# Charger_Board_3_Sam_Test.net
KiCad netlist of a schematic drawn in EAGLE
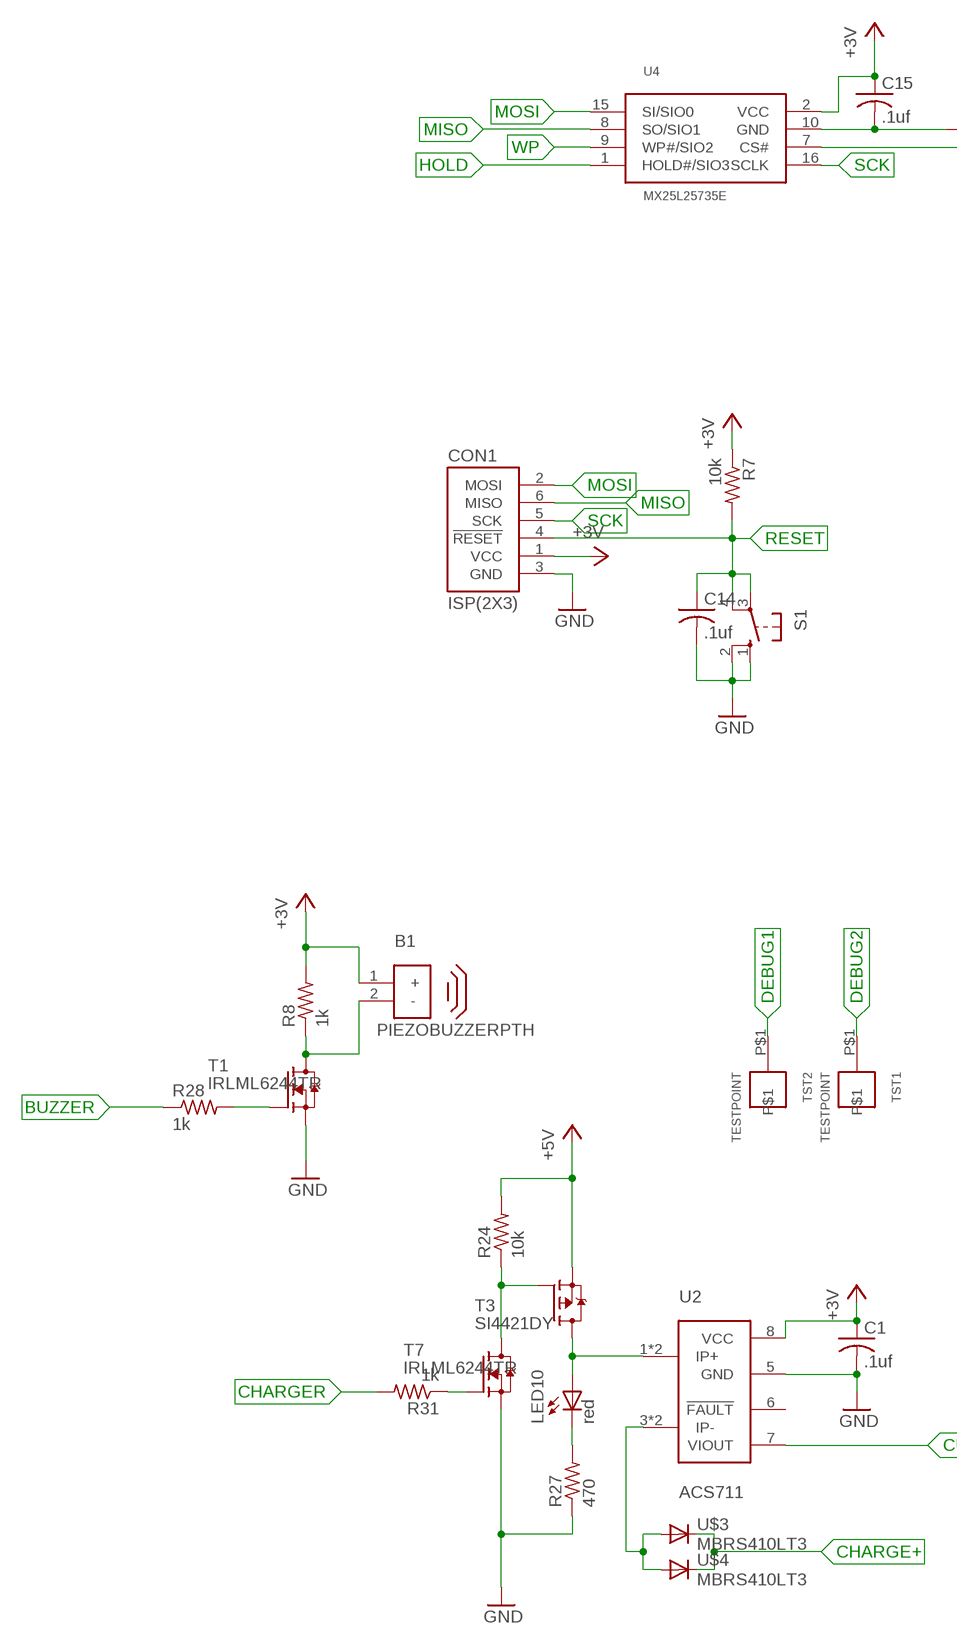
[diagram p0: schematic, sheet 1, part 1 of 2]
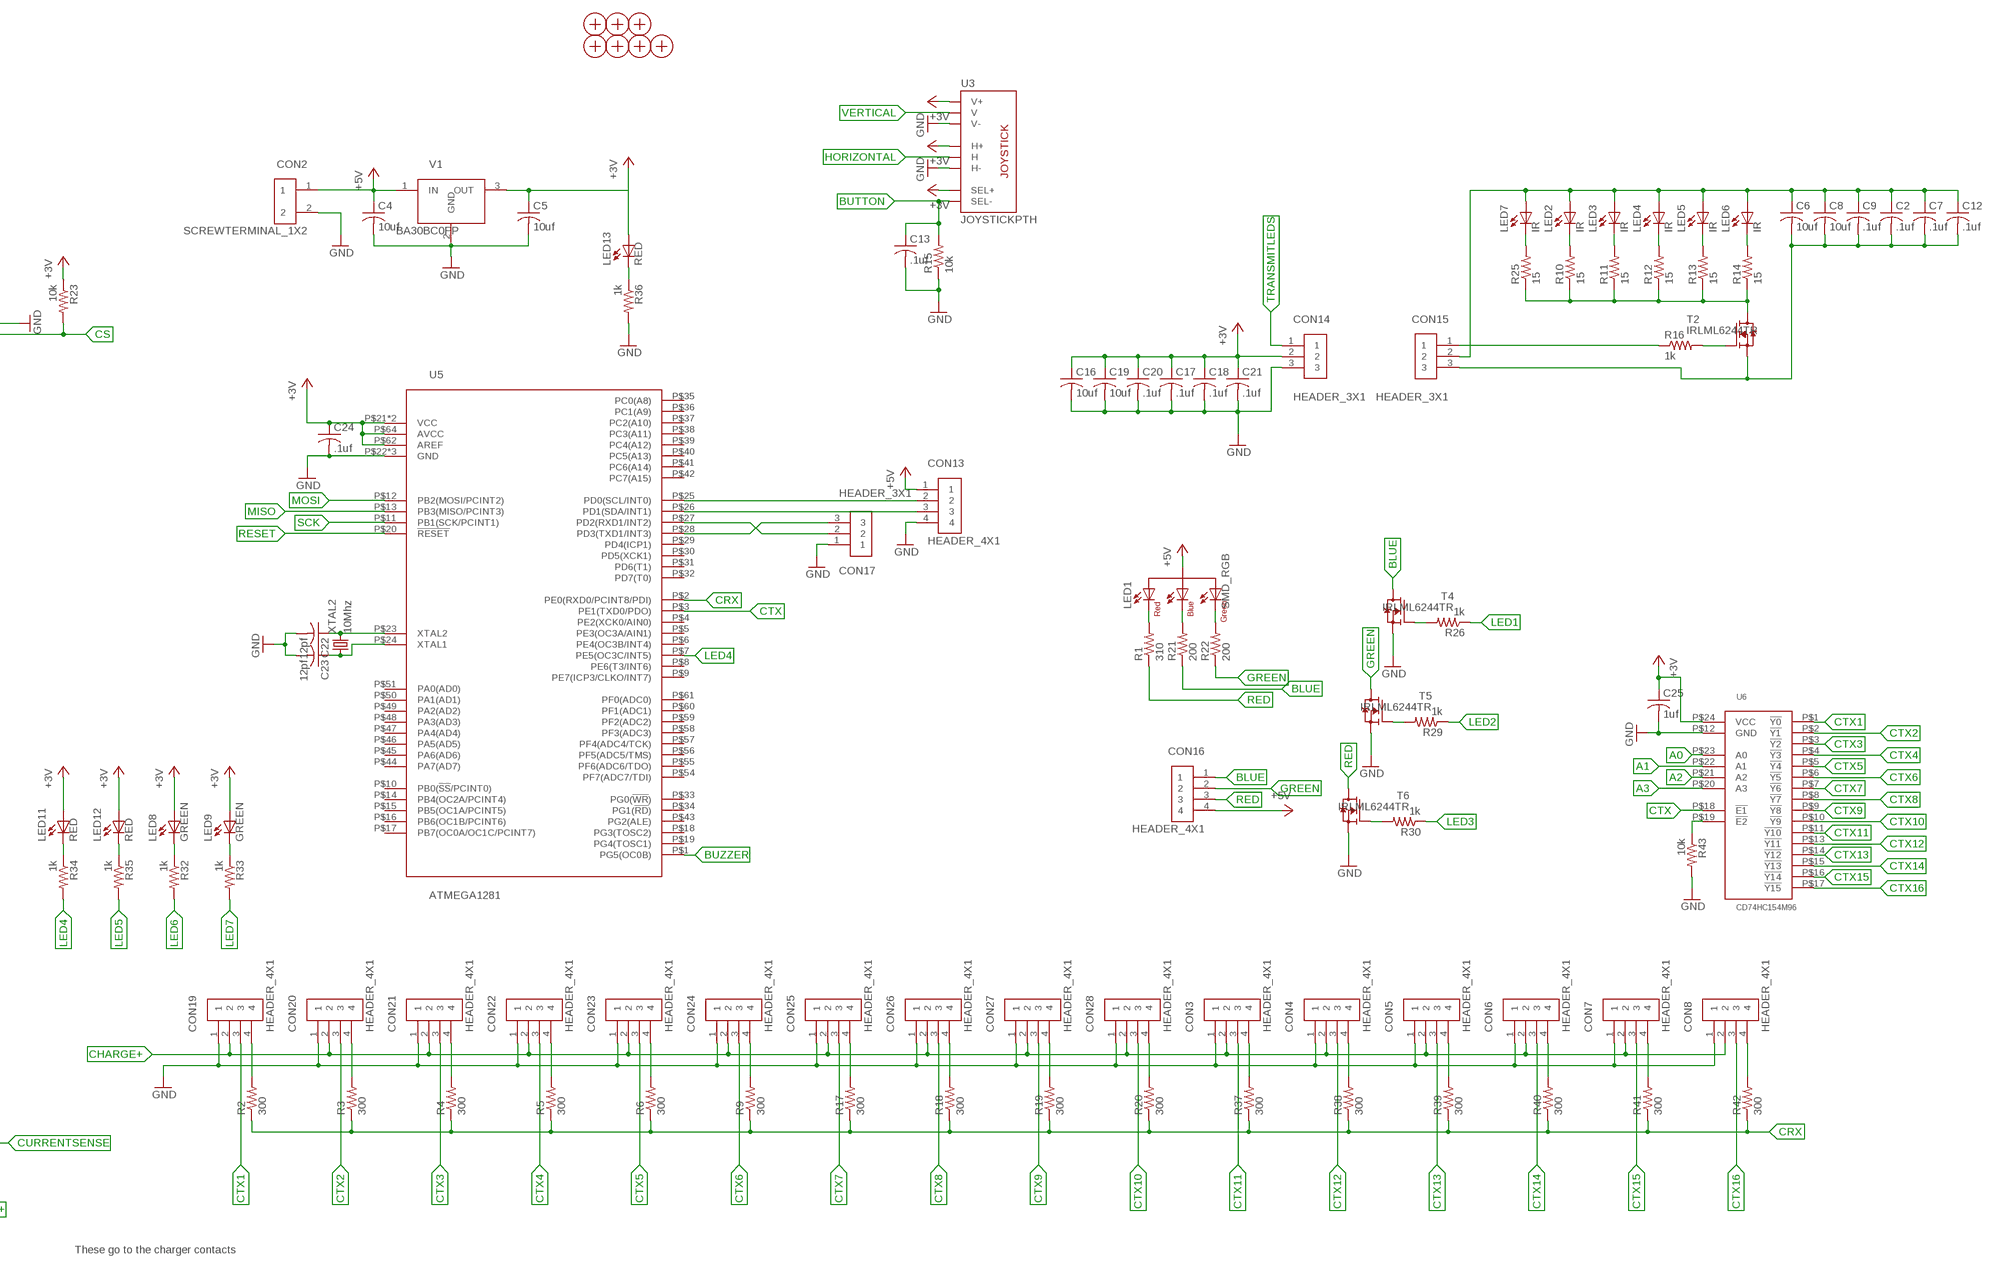
[diagram p1: schematic, sheet 1, part 2 of 2]

(export (version "E")
  (design (tool "Eeschema 10.0.6"))
  (components
    (comp (ref "B1")
      (value "PIEZOBUZZERPTH")
      (footprint "eagle-import:PIEZOBUZZER")
      (libsource (lib "eagle-import") (part "PIEZOBUZZERPTH"))
    )
    (comp (ref "C1")
      (value ".1uf")
      (footprint "eagle-import:0603")
      (libsource (lib "eagle-import") (part "CAP0603"))
    )
    (comp (ref "C2")
      (value ".1uf")
      (footprint "eagle-import:0603")
      (libsource (lib "eagle-import") (part "CAP0603"))
    )
    (comp (ref "C4")
      (value "10uf")
      (footprint "eagle-import:0805")
      (libsource (lib "eagle-import") (part "CAP0805"))
    )
    (comp (ref "C5")
      (value "10uf")
      (footprint "eagle-import:0805")
      (libsource (lib "eagle-import") (part "CAP0805"))
    )
    (comp (ref "C6")
      (value "10uf")
      (footprint "eagle-import:0805")
      (libsource (lib "eagle-import") (part "CAP0805"))
    )
    (comp (ref "C7")
      (value ".1uf")
      (footprint "eagle-import:0603")
      (libsource (lib "eagle-import") (part "CAP0603"))
    )
    (comp (ref "C8")
      (value "10uf")
      (footprint "eagle-import:0805")
      (libsource (lib "eagle-import") (part "CAP0805"))
    )
    (comp (ref "C9")
      (value ".1uf")
      (footprint "eagle-import:0603")
      (libsource (lib "eagle-import") (part "CAP0603"))
    )
    (comp (ref "C12")
      (value ".1uf")
      (footprint "eagle-import:0603")
      (libsource (lib "eagle-import") (part "CAP0603"))
    )
    (comp (ref "C13")
      (value ".1uf")
      (footprint "eagle-import:0603")
      (libsource (lib "eagle-import") (part "CAP0603"))
    )
    (comp (ref "C14")
      (value ".1uf")
      (footprint "eagle-import:0603")
      (libsource (lib "eagle-import") (part "CAP0603"))
    )
    (comp (ref "C15")
      (value ".1uf")
      (footprint "eagle-import:0603")
      (libsource (lib "eagle-import") (part "CAP0603"))
    )
    (comp (ref "C16")
      (value "10uf")
      (footprint "eagle-import:0805")
      (libsource (lib "eagle-import") (part "CAP0805"))
    )
    (comp (ref "C17")
      (value ".1uf")
      (footprint "eagle-import:0603")
      (libsource (lib "eagle-import") (part "CAP0603"))
    )
    (comp (ref "C18")
      (value ".1uf")
      (footprint "eagle-import:0603")
      (libsource (lib "eagle-import") (part "CAP0603"))
    )
    (comp (ref "C19")
      (value "10uf")
      (footprint "eagle-import:0805")
      (libsource (lib "eagle-import") (part "CAP0805"))
    )
    (comp (ref "C20")
      (value ".1uf")
      (footprint "eagle-import:0603")
      (libsource (lib "eagle-import") (part "CAP0603"))
    )
    (comp (ref "C21")
      (value ".1uf")
      (footprint "eagle-import:0603")
      (libsource (lib "eagle-import") (part "CAP0603"))
    )
    (comp (ref "C22")
      (value "12pf")
      (footprint "eagle-import:0603")
      (libsource (lib "eagle-import") (part "CAP0603"))
    )
    (comp (ref "C23")
      (value "12pf")
      (footprint "eagle-import:0603")
      (libsource (lib "eagle-import") (part "CAP0603"))
    )
    (comp (ref "C24")
      (value ".1uf")
      (footprint "eagle-import:0603")
      (libsource (lib "eagle-import") (part "CAP0603"))
    )
    (comp (ref "C25")
      (value "1uf")
      (footprint "eagle-import:0603")
      (libsource (lib "eagle-import") (part "CAP0603"))
    )
    (comp (ref "CON1")
      (value "ISP(2X3)")
      (footprint "eagle-import:PINHEADER(2X3)")
      (libsource (lib "eagle-import") (part "ISP(2X3)"))
    )
    (comp (ref "CON2")
      (value "SCREWTERMINAL_1X2")
      (footprint "eagle-import:SCREWTERMINAL_1X2")
      (libsource (lib "eagle-import") (part "SCREWTERMINAL_1X2"))
    )
    (comp (ref "CON3")
      (value "HEADER_4X1")
      (footprint "eagle-import:4PINHEADER_.100_")
      (libsource (lib "eagle-import") (part "HEADER_4X1"))
    )
    (comp (ref "CON4")
      (value "HEADER_4X1")
      (footprint "eagle-import:4PINHEADER_.100_")
      (libsource (lib "eagle-import") (part "HEADER_4X1"))
    )
    (comp (ref "CON5")
      (value "HEADER_4X1")
      (footprint "eagle-import:4PINHEADER_.100_")
      (libsource (lib "eagle-import") (part "HEADER_4X1"))
    )
    (comp (ref "CON6")
      (value "HEADER_4X1")
      (footprint "eagle-import:4PINHEADER_.100_")
      (libsource (lib "eagle-import") (part "HEADER_4X1"))
    )
    (comp (ref "CON7")
      (value "HEADER_4X1")
      (footprint "eagle-import:4PINHEADER_.100_")
      (libsource (lib "eagle-import") (part "HEADER_4X1"))
    )
    (comp (ref "CON8")
      (value "HEADER_4X1")
      (footprint "eagle-import:4PINHEADER_.100_")
      (libsource (lib "eagle-import") (part "HEADER_4X1"))
    )
    (comp (ref "CON13")
      (value "HEADER_4X1")
      (footprint "eagle-import:4PINHEADER_.100_")
      (libsource (lib "eagle-import") (part "HEADER_4X1"))
    )
    (comp (ref "CON14")
      (value "HEADER_3X1")
      (footprint "eagle-import:3PINHEADER_.100_")
      (libsource (lib "eagle-import") (part "HEADER_3X1"))
    )
    (comp (ref "CON15")
      (value "HEADER_3X1")
      (footprint "eagle-import:3PINHEADER_.100_")
      (libsource (lib "eagle-import") (part "HEADER_3X1"))
    )
    (comp (ref "CON16")
      (value "HEADER_4X1")
      (footprint "eagle-import:4PINHEADER_.100_")
      (libsource (lib "eagle-import") (part "HEADER_4X1"))
    )
    (comp (ref "CON17")
      (value "HEADER_3X1")
      (footprint "eagle-import:3PINHEADER_.100_")
      (libsource (lib "eagle-import") (part "HEADER_3X1"))
    )
    (comp (ref "CON19")
      (value "HEADER_4X1")
      (footprint "eagle-import:4PINHEADER_.100_")
      (libsource (lib "eagle-import") (part "HEADER_4X1"))
    )
    (comp (ref "CON20")
      (value "HEADER_4X1")
      (footprint "eagle-import:4PINHEADER_.100_")
      (libsource (lib "eagle-import") (part "HEADER_4X1"))
    )
    (comp (ref "CON21")
      (value "HEADER_4X1")
      (footprint "eagle-import:4PINHEADER_.100_")
      (libsource (lib "eagle-import") (part "HEADER_4X1"))
    )
    (comp (ref "CON22")
      (value "HEADER_4X1")
      (footprint "eagle-import:4PINHEADER_.100_")
      (libsource (lib "eagle-import") (part "HEADER_4X1"))
    )
    (comp (ref "CON23")
      (value "HEADER_4X1")
      (footprint "eagle-import:4PINHEADER_.100_")
      (libsource (lib "eagle-import") (part "HEADER_4X1"))
    )
    (comp (ref "CON24")
      (value "HEADER_4X1")
      (footprint "eagle-import:4PINHEADER_.100_")
      (libsource (lib "eagle-import") (part "HEADER_4X1"))
    )
    (comp (ref "CON25")
      (value "HEADER_4X1")
      (footprint "eagle-import:4PINHEADER_.100_")
      (libsource (lib "eagle-import") (part "HEADER_4X1"))
    )
    (comp (ref "CON26")
      (value "HEADER_4X1")
      (footprint "eagle-import:4PINHEADER_.100_")
      (libsource (lib "eagle-import") (part "HEADER_4X1"))
    )
    (comp (ref "CON27")
      (value "HEADER_4X1")
      (footprint "eagle-import:4PINHEADER_.100_")
      (libsource (lib "eagle-import") (part "HEADER_4X1"))
    )
    (comp (ref "CON28")
      (value "HEADER_4X1")
      (footprint "eagle-import:4PINHEADER_.100_")
      (libsource (lib "eagle-import") (part "HEADER_4X1"))
    )
    (comp (ref "H1")
      (value "MOUNTINGHOLE")
      (footprint "eagle-import:MOUNTINGHOLE")
      (libsource (lib "eagle-import") (part "MOUNTINGHOLE"))
    )
    (comp (ref "H2")
      (value "MOUNTINGHOLE")
      (footprint "eagle-import:MOUNTINGHOLE")
      (libsource (lib "eagle-import") (part "MOUNTINGHOLE"))
    )
    (comp (ref "H3")
      (value "MOUNTINGHOLE")
      (footprint "eagle-import:MOUNTINGHOLE")
      (libsource (lib "eagle-import") (part "MOUNTINGHOLE"))
    )
    (comp (ref "H4")
      (value "MOUNTINGHOLE")
      (footprint "eagle-import:MOUNTINGHOLE")
      (libsource (lib "eagle-import") (part "MOUNTINGHOLE"))
    )
    (comp (ref "H5")
      (value "MOUNTINGHOLE")
      (footprint "eagle-import:MOUNTINGHOLE")
      (libsource (lib "eagle-import") (part "MOUNTINGHOLE"))
    )
    (comp (ref "H6")
      (value "MOUNTINGHOLE")
      (footprint "eagle-import:MOUNTINGHOLE")
      (libsource (lib "eagle-import") (part "MOUNTINGHOLE"))
    )
    (comp (ref "H7")
      (value "MOUNTINGHOLE")
      (footprint "eagle-import:MOUNTINGHOLE")
      (libsource (lib "eagle-import") (part "MOUNTINGHOLE"))
    )
    (comp (ref "LED1")
      (value "SMD_RGB")
      (footprint "eagle-import:PLCC4")
      (libsource (lib "eagle-import") (part "SMD_RGB"))
    )
    (comp (ref "LED2")
      (value "IR")
      (footprint "eagle-import:5MM_LED_RA")
      (libsource (lib "eagle-import") (part "LED5MMRA"))
    )
    (comp (ref "LED3")
      (value "IR")
      (footprint "eagle-import:5MM_LED_RA")
      (libsource (lib "eagle-import") (part "LED5MMRA"))
    )
    (comp (ref "LED4")
      (value "IR")
      (footprint "eagle-import:5MM_LED_RA")
      (libsource (lib "eagle-import") (part "LED5MMRA"))
    )
    (comp (ref "LED5")
      (value "IR")
      (footprint "eagle-import:5MM_LED_RA")
      (libsource (lib "eagle-import") (part "LED5MMRA"))
    )
    (comp (ref "LED6")
      (value "IR")
      (footprint "eagle-import:5MM_LED_RA")
      (libsource (lib "eagle-import") (part "LED5MMRA"))
    )
    (comp (ref "LED7")
      (value "IR")
      (footprint "eagle-import:5MM_LED_RA")
      (libsource (lib "eagle-import") (part "LED5MMRA"))
    )
    (comp (ref "LED8")
      (value "GREEN")
      (footprint "eagle-import:LED0603")
      (libsource (lib "eagle-import") (part "LED0603"))
    )
    (comp (ref "LED9")
      (value "GREEN")
      (footprint "eagle-import:LED0603")
      (libsource (lib "eagle-import") (part "LED0603"))
    )
    (comp (ref "LED10")
      (value "red")
      (footprint "eagle-import:LED0603")
      (libsource (lib "eagle-import") (part "LED0603"))
    )
    (comp (ref "LED11")
      (value "RED")
      (footprint "eagle-import:LED0603")
      (libsource (lib "eagle-import") (part "LED0603"))
    )
    (comp (ref "LED12")
      (value "RED")
      (footprint "eagle-import:LED0603")
      (libsource (lib "eagle-import") (part "LED0603"))
    )
    (comp (ref "LED13")
      (value "RED")
      (footprint "eagle-import:LED0603")
      (libsource (lib "eagle-import") (part "LED0603"))
    )
    (comp (ref "R1")
      (value "310")
      (footprint "eagle-import:0603")
      (libsource (lib "eagle-import") (part "RES0603"))
    )
    (comp (ref "R2")
      (value "300")
      (footprint "eagle-import:0603")
      (libsource (lib "eagle-import") (part "RES0603"))
    )
    (comp (ref "R3")
      (value "300")
      (footprint "eagle-import:0603")
      (libsource (lib "eagle-import") (part "RES0603"))
    )
    (comp (ref "R4")
      (value "300")
      (footprint "eagle-import:0603")
      (libsource (lib "eagle-import") (part "RES0603"))
    )
    (comp (ref "R5")
      (value "300")
      (footprint "eagle-import:0603")
      (libsource (lib "eagle-import") (part "RES0603"))
    )
    (comp (ref "R6")
      (value "300")
      (footprint "eagle-import:0603")
      (libsource (lib "eagle-import") (part "RES0603"))
    )
    (comp (ref "R7")
      (value "10k")
      (footprint "eagle-import:0603")
      (libsource (lib "eagle-import") (part "RES0603"))
    )
    (comp (ref "R8")
      (value "1k")
      (footprint "eagle-import:0603")
      (libsource (lib "eagle-import") (part "RES0603"))
    )
    (comp (ref "R9")
      (value "300")
      (footprint "eagle-import:0603")
      (libsource (lib "eagle-import") (part "RES0603"))
    )
    (comp (ref "R10")
      (value "15")
      (footprint "eagle-import:0603")
      (libsource (lib "eagle-import") (part "RES0603"))
    )
    (comp (ref "R11")
      (value "15")
      (footprint "eagle-import:0603")
      (libsource (lib "eagle-import") (part "RES0603"))
    )
    (comp (ref "R12")
      (value "15")
      (footprint "eagle-import:0603")
      (libsource (lib "eagle-import") (part "RES0603"))
    )
    (comp (ref "R13")
      (value "15")
      (footprint "eagle-import:0603")
      (libsource (lib "eagle-import") (part "RES0603"))
    )
    (comp (ref "R14")
      (value "15")
      (footprint "eagle-import:0603")
      (libsource (lib "eagle-import") (part "RES0603"))
    )
    (comp (ref "R15")
      (value "10k")
      (footprint "eagle-import:0603")
      (libsource (lib "eagle-import") (part "RES0603"))
    )
    (comp (ref "R16")
      (value "1k")
      (footprint "eagle-import:0603")
      (libsource (lib "eagle-import") (part "RES0603"))
    )
    (comp (ref "R17")
      (value "300")
      (footprint "eagle-import:0603")
      (libsource (lib "eagle-import") (part "RES0603"))
    )
    (comp (ref "R18")
      (value "300")
      (footprint "eagle-import:0603")
      (libsource (lib "eagle-import") (part "RES0603"))
    )
    (comp (ref "R19")
      (value "300")
      (footprint "eagle-import:0603")
      (libsource (lib "eagle-import") (part "RES0603"))
    )
    (comp (ref "R20")
      (value "300")
      (footprint "eagle-import:0603")
      (libsource (lib "eagle-import") (part "RES0603"))
    )
    (comp (ref "R21")
      (value "200")
      (footprint "eagle-import:0603")
      (libsource (lib "eagle-import") (part "RES0603"))
    )
    (comp (ref "R22")
      (value "200")
      (footprint "eagle-import:0603")
      (libsource (lib "eagle-import") (part "RES0603"))
    )
    (comp (ref "R23")
      (value "10k")
      (footprint "eagle-import:0603")
      (libsource (lib "eagle-import") (part "RES0603"))
    )
    (comp (ref "R24")
      (value "10k")
      (footprint "eagle-import:0603")
      (libsource (lib "eagle-import") (part "RES0603"))
    )
    (comp (ref "R25")
      (value "15")
      (footprint "eagle-import:0603")
      (libsource (lib "eagle-import") (part "RES0603"))
    )
    (comp (ref "R26")
      (value "1k")
      (footprint "eagle-import:0603")
      (libsource (lib "eagle-import") (part "RES0603"))
    )
    (comp (ref "R27")
      (value "470")
      (footprint "eagle-import:0603")
      (libsource (lib "eagle-import") (part "RES0603"))
    )
    (comp (ref "R28")
      (value "1k")
      (footprint "eagle-import:0603")
      (libsource (lib "eagle-import") (part "RES0603"))
    )
    (comp (ref "R29")
      (value "1k")
      (footprint "eagle-import:0603")
      (libsource (lib "eagle-import") (part "RES0603"))
    )
    (comp (ref "R30")
      (value "1k")
      (footprint "eagle-import:0603")
      (libsource (lib "eagle-import") (part "RES0603"))
    )
    (comp (ref "R31")
      (value "1k")
      (footprint "eagle-import:0603")
      (libsource (lib "eagle-import") (part "RES0603"))
    )
    (comp (ref "R32")
      (value "1k")
      (footprint "eagle-import:0603")
      (libsource (lib "eagle-import") (part "RES0603"))
    )
    (comp (ref "R33")
      (value "1k")
      (footprint "eagle-import:0603")
      (libsource (lib "eagle-import") (part "RES0603"))
    )
    (comp (ref "R34")
      (value "1k")
      (footprint "eagle-import:0603")
      (libsource (lib "eagle-import") (part "RES0603"))
    )
    (comp (ref "R35")
      (value "1k")
      (footprint "eagle-import:0603")
      (libsource (lib "eagle-import") (part "RES0603"))
    )
    (comp (ref "R36")
      (value "1k")
      (footprint "eagle-import:0603")
      (libsource (lib "eagle-import") (part "RES0603"))
    )
    (comp (ref "R37")
      (value "300")
      (footprint "eagle-import:0603")
      (libsource (lib "eagle-import") (part "RES0603"))
    )
    (comp (ref "R38")
      (value "300")
      (footprint "eagle-import:0603")
      (libsource (lib "eagle-import") (part "RES0603"))
    )
    (comp (ref "R39")
      (value "300")
      (footprint "eagle-import:0603")
      (libsource (lib "eagle-import") (part "RES0603"))
    )
    (comp (ref "R40")
      (value "300")
      (footprint "eagle-import:0603")
      (libsource (lib "eagle-import") (part "RES0603"))
    )
    (comp (ref "R41")
      (value "300")
      (footprint "eagle-import:0603")
      (libsource (lib "eagle-import") (part "RES0603"))
    )
    (comp (ref "R42")
      (value "300")
      (footprint "eagle-import:0603")
      (libsource (lib "eagle-import") (part "RES0603"))
    )
    (comp (ref "R43")
      (value "10k")
      (footprint "eagle-import:0603")
      (libsource (lib "eagle-import") (part "RES0603"))
    )
    (comp (ref "S1")
      (value "10-XX")
      (footprint "eagle-import:B3F-10XX")
      (fields (field (name "MPN") "B3F-1000"))
      (libsource (lib "eagle-import") (part "10-XX"))
    )
    (comp (ref "T1")
      (value "IRLML6244TR")
      (footprint "eagle-import:SOT23")
      (libsource (lib "eagle-import") (part "IRLML6244TR"))
    )
    (comp (ref "T2")
      (value "IRLML6244TR")
      (footprint "eagle-import:SOT23")
      (libsource (lib "eagle-import") (part "IRLML6244TR"))
    )
    (comp (ref "T3")
      (value "SI4421DY")
      (footprint "eagle-import:S0-8")
      (libsource (lib "eagle-import") (part "SI4421DY"))
    )
    (comp (ref "T4")
      (value "IRLML6244TR")
      (footprint "eagle-import:SOT23")
      (libsource (lib "eagle-import") (part "IRLML6244TR"))
    )
    (comp (ref "T5")
      (value "IRLML6244TR")
      (footprint "eagle-import:SOT23")
      (libsource (lib "eagle-import") (part "IRLML6244TR"))
    )
    (comp (ref "T6")
      (value "IRLML6244TR")
      (footprint "eagle-import:SOT23")
      (libsource (lib "eagle-import") (part "IRLML6244TR"))
    )
    (comp (ref "T7")
      (value "IRLML6244TR")
      (footprint "eagle-import:SOT23")
      (libsource (lib "eagle-import") (part "IRLML6244TR"))
    )
    (comp (ref "TST1")
      (value "TESTPOINT")
      (footprint "eagle-import:TESTPOINT")
      (libsource (lib "eagle-import") (part "TESTPOINT"))
    )
    (comp (ref "TST2")
      (value "TESTPOINT")
      (footprint "eagle-import:TESTPOINT")
      (libsource (lib "eagle-import") (part "TESTPOINT"))
    )
    (comp (ref "U$3")
      (value "MBRS410LT3")
      (footprint "eagle-import:SMD_DIODE")
      (libsource (lib "eagle-import") (part "MBRS410LT3"))
    )
    (comp (ref "U$4")
      (value "MBRS410LT3")
      (footprint "eagle-import:SMD_DIODE")
      (libsource (lib "eagle-import") (part "MBRS410LT3"))
    )
    (comp (ref "U2")
      (value "ACS711")
      (footprint "eagle-import:8SOIC")
      (libsource (lib "eagle-import") (part "ACS711"))
    )
    (comp (ref "U3")
      (value "JOYSTICKPTH")
      (footprint "eagle-import:JOYSTICK")
      (libsource (lib "eagle-import") (part "JOYSTICKPTH"))
    )
    (comp (ref "U4")
      (value "MX25L25735E")
      (footprint "eagle-import:SOIC16R")
      (libsource (lib "eagle-import") (part "MX25L25735E"))
    )
    (comp (ref "U5")
      (value "ATMEGA1281")
      (footprint "eagle-import:TQFP64")
      (libsource (lib "eagle-import") (part "ATMEGA1281"))
    )
    (comp (ref "U6")
      (value "CD74HC154M96")
      (footprint "eagle-import:24SOIC")
      (libsource (lib "eagle-import") (part "CD74HC154M96"))
    )
    (comp (ref "V1")
      (value "BA30BC0FP")
      (footprint "eagle-import:DPAK")
      (libsource (lib "eagle-import") (part "BA30BC0FP"))
    )
    (comp (ref "XTAL2")
      (value "10Mhz")
      (footprint "eagle-import:SMDXTAL")
      (libsource (lib "eagle-import") (part "NX5032GA-10.000000MHZ"))
    )
  )
  (nets
    (net (code "1") (name "+3V") (class "Default")
      (node (ref "B1") (pin "1") (pinfunction "+_1") (pintype "bidirectional"))
      (node (ref "C1") (pin "1") (pinfunction "1_1") (pintype "passive"))
      (node (ref "C15") (pin "1") (pinfunction "1_1") (pintype "passive"))
      (node (ref "C16") (pin "1") (pinfunction "1_1") (pintype "passive"))
      (node (ref "C17") (pin "1") (pinfunction "1_1") (pintype "passive"))
      (node (ref "C18") (pin "1") (pinfunction "1_1") (pintype "passive"))
      (node (ref "C19") (pin "1") (pinfunction "1_1") (pintype "passive"))
      (node (ref "C20") (pin "1") (pinfunction "1_1") (pintype "passive"))
      (node (ref "C21") (pin "1") (pinfunction "1_1") (pintype "passive"))
      (node (ref "C24") (pin "1") (pinfunction "1_1") (pintype "passive"))
      (node (ref "C25") (pin "1") (pinfunction "1_1") (pintype "passive"))
      (node (ref "C5") (pin "1") (pinfunction "1_1") (pintype "passive"))
      (node (ref "CON1") (pin "1") (pinfunction "VCC_1") (pintype "bidirectional"))
      (node (ref "CON14") (pin "2") (pinfunction "2_2") (pintype "bidirectional"))
      (node (ref "LED11") (pin "2") (pinfunction "A_2") (pintype "passive"))
      (node (ref "LED12") (pin "2") (pinfunction "A_2") (pintype "passive"))
      (node (ref "LED13") (pin "2") (pinfunction "A_2") (pintype "passive"))
      (node (ref "LED8") (pin "2") (pinfunction "A_2") (pintype "passive"))
      (node (ref "LED9") (pin "2") (pinfunction "A_2") (pintype "passive"))
      (node (ref "R23") (pin "1") (pinfunction "1_1") (pintype "passive"))
      (node (ref "R7") (pin "1") (pinfunction "1_1") (pintype "passive"))
      (node (ref "R8") (pin "2") (pinfunction "2_2") (pintype "passive"))
      (node (ref "U2") (pin "8") (pinfunction "VCC_8") (pintype "bidirectional"))
      (node (ref "U3") (pin "B1A") (pinfunction "SEL+_B1A") (pintype "bidirectional"))
      (node (ref "U3") (pin "H1") (pinfunction "H+_H1") (pintype "bidirectional"))
      (node (ref "U3") (pin "V1") (pinfunction "V+_V1") (pintype "bidirectional"))
      (node (ref "U4") (pin "2") (pinfunction "VCC_2") (pintype "bidirectional"))
      (node (ref "U5") (pin "P$21") (pinfunction "VCC_P$21") (pintype "bidirectional"))
      (node (ref "U5") (pin "P$52") (pinfunction "VCC_P$52") (pintype "bidirectional"))
      (node (ref "U5") (pin "P$62") (pinfunction "AREF_P$62") (pintype "bidirectional"))
      (node (ref "U5") (pin "P$64") (pinfunction "AVCC_P$64") (pintype "bidirectional"))
      (node (ref "U6") (pin "P$24") (pinfunction "VCC_P$24") (pintype "bidirectional"))
      (node (ref "V1") (pin "3") (pinfunction "OUT_3") (pintype "bidirectional"))
    )
    (net (code "2") (name "+5V") (class "Default")
      (node (ref "C4") (pin "1") (pinfunction "1_1") (pintype "passive"))
      (node (ref "CON13") (pin "1") (pinfunction "1_1") (pintype "bidirectional"))
      (node (ref "CON16") (pin "4") (pinfunction "4_4") (pintype "bidirectional"))
      (node (ref "CON2") (pin "1") (pinfunction "1_1") (pintype "bidirectional"))
      (node (ref "LED1") (pin "2") (pinfunction "COMMONANODE_2") (pintype "passive"))
      (node (ref "R24") (pin "2") (pinfunction "2_2") (pintype "passive"))
      (node (ref "T3") (pin "1") (pinfunction "S_1") (pintype "passive"))
      (node (ref "T3") (pin "2") (pinfunction "S_2") (pintype "passive"))
      (node (ref "T3") (pin "3") (pinfunction "S_3") (pintype "passive"))
      (node (ref "V1") (pin "1") (pinfunction "IN_1") (pintype "bidirectional"))
    )
    (net (code "3") (name "A0") (class "Default")
      (node (ref "U6") (pin "P$23") (pinfunction "A0_P$23") (pintype "bidirectional"))
    )
    (net (code "4") (name "A1") (class "Default")
      (node (ref "U6") (pin "P$22") (pinfunction "A1_P$22") (pintype "bidirectional"))
    )
    (net (code "5") (name "A2") (class "Default")
      (node (ref "U6") (pin "P$21") (pinfunction "A2_P$21") (pintype "bidirectional"))
    )
    (net (code "6") (name "A3") (class "Default")
      (node (ref "U6") (pin "P$20") (pinfunction "A3_P$20") (pintype "bidirectional"))
    )
    (net (code "7") (name "BLUE") (class "Default")
      (node (ref "CON16") (pin "1") (pinfunction "1_1") (pintype "bidirectional"))
      (node (ref "R21") (pin "1") (pinfunction "1_1") (pintype "passive"))
      (node (ref "T4") (pin "3") (pinfunction "D_3") (pintype "passive"))
    )
    (net (code "8") (name "BUTTON") (class "Default")
      (node (ref "C13") (pin "1") (pinfunction "1_1") (pintype "passive"))
      (node (ref "R15") (pin "2") (pinfunction "2_2") (pintype "passive"))
      (node (ref "U3") (pin "B2A") (pinfunction "SEL-_B2A") (pintype "bidirectional"))
    )
    (net (code "9") (name "BUZZER") (class "Default")
      (node (ref "R28") (pin "1") (pinfunction "1_1") (pintype "passive"))
      (node (ref "U5") (pin "P$1") (pinfunction "PG5(OC0B)_P$1") (pintype "bidirectional"))
    )
    (net (code "10") (name "CHARGE+") (class "Default")
      (node (ref "CON19") (pin "2") (pinfunction "2_2") (pintype "bidirectional"))
      (node (ref "CON20") (pin "2") (pinfunction "2_2") (pintype "bidirectional"))
      (node (ref "CON21") (pin "2") (pinfunction "2_2") (pintype "bidirectional"))
      (node (ref "CON22") (pin "2") (pinfunction "2_2") (pintype "bidirectional"))
      (node (ref "CON23") (pin "2") (pinfunction "2_2") (pintype "bidirectional"))
      (node (ref "CON24") (pin "2") (pinfunction "2_2") (pintype "bidirectional"))
      (node (ref "CON25") (pin "2") (pinfunction "2_2") (pintype "bidirectional"))
      (node (ref "CON26") (pin "2") (pinfunction "2_2") (pintype "bidirectional"))
      (node (ref "CON27") (pin "2") (pinfunction "2_2") (pintype "bidirectional"))
      (node (ref "CON28") (pin "2") (pinfunction "2_2") (pintype "bidirectional"))
      (node (ref "CON3") (pin "2") (pinfunction "2_2") (pintype "bidirectional"))
      (node (ref "CON4") (pin "2") (pinfunction "2_2") (pintype "bidirectional"))
      (node (ref "CON5") (pin "2") (pinfunction "2_2") (pintype "bidirectional"))
      (node (ref "CON6") (pin "2") (pinfunction "2_2") (pintype "bidirectional"))
      (node (ref "CON7") (pin "2") (pinfunction "2_2") (pintype "bidirectional"))
      (node (ref "CON8") (pin "2") (pinfunction "2_2") (pintype "bidirectional"))
      (node (ref "U$3") (pin "2") (pinfunction "C_2") (pintype "passive"))
      (node (ref "U$4") (pin "2") (pinfunction "C_2") (pintype "passive"))
    )
    (net (code "11") (name "CHARGER") (class "Default")
      (node (ref "R31") (pin "2") (pinfunction "2_2") (pintype "passive"))
    )
    (net (code "12") (name "CRX") (class "Default")
      (node (ref "R17") (pin "1") (pinfunction "1_1") (pintype "passive"))
      (node (ref "R18") (pin "1") (pinfunction "1_1") (pintype "passive"))
      (node (ref "R19") (pin "1") (pinfunction "1_1") (pintype "passive"))
      (node (ref "R2") (pin "1") (pinfunction "1_1") (pintype "passive"))
      (node (ref "R20") (pin "1") (pinfunction "1_1") (pintype "passive"))
      (node (ref "R3") (pin "1") (pinfunction "1_1") (pintype "passive"))
      (node (ref "R37") (pin "1") (pinfunction "1_1") (pintype "passive"))
      (node (ref "R38") (pin "1") (pinfunction "1_1") (pintype "passive"))
      (node (ref "R39") (pin "1") (pinfunction "1_1") (pintype "passive"))
      (node (ref "R4") (pin "1") (pinfunction "1_1") (pintype "passive"))
      (node (ref "R40") (pin "1") (pinfunction "1_1") (pintype "passive"))
      (node (ref "R41") (pin "1") (pinfunction "1_1") (pintype "passive"))
      (node (ref "R42") (pin "1") (pinfunction "1_1") (pintype "passive"))
      (node (ref "R5") (pin "1") (pinfunction "1_1") (pintype "passive"))
      (node (ref "R6") (pin "1") (pinfunction "1_1") (pintype "passive"))
      (node (ref "R9") (pin "1") (pinfunction "1_1") (pintype "passive"))
      (node (ref "U5") (pin "P$2") (pinfunction "PE0(RXD0/PCINT8/PDI)_P$2") (pintype "bidirectional"))
    )
    (net (code "13") (name "CS") (class "Default")
      (node (ref "R23") (pin "2") (pinfunction "2_2") (pintype "passive"))
      (node (ref "U4") (pin "7") (pinfunction "CS#_7") (pintype "bidirectional"))
    )
    (net (code "14") (name "CTX") (class "Default")
      (node (ref "U5") (pin "P$3") (pinfunction "PE1(TXD0/PDO)_P$3") (pintype "bidirectional"))
      (node (ref "U6") (pin "P$18") (pinfunction "~{E1}_P$18") (pintype "bidirectional"))
    )
    (net (code "15") (name "CTX1") (class "Default")
      (node (ref "CON19") (pin "3") (pinfunction "3_3") (pintype "bidirectional"))
      (node (ref "U6") (pin "P$1") (pinfunction "~{Y0}_P$1") (pintype "bidirectional"))
    )
    (net (code "16") (name "CTX2") (class "Default")
      (node (ref "CON20") (pin "3") (pinfunction "3_3") (pintype "bidirectional"))
      (node (ref "U6") (pin "P$2") (pinfunction "~{Y1}_P$2") (pintype "bidirectional"))
    )
    (net (code "17") (name "CTX3") (class "Default")
      (node (ref "CON21") (pin "3") (pinfunction "3_3") (pintype "bidirectional"))
      (node (ref "U6") (pin "P$3") (pinfunction "~{Y2}_P$3") (pintype "bidirectional"))
    )
    (net (code "18") (name "CTX4") (class "Default")
      (node (ref "CON22") (pin "3") (pinfunction "3_3") (pintype "bidirectional"))
      (node (ref "U6") (pin "P$4") (pinfunction "~{Y3}_P$4") (pintype "bidirectional"))
    )
    (net (code "19") (name "CTX5") (class "Default")
      (node (ref "CON23") (pin "3") (pinfunction "3_3") (pintype "bidirectional"))
      (node (ref "U6") (pin "P$5") (pinfunction "~{Y4}_P$5") (pintype "bidirectional"))
    )
    (net (code "20") (name "CTX6") (class "Default")
      (node (ref "CON24") (pin "3") (pinfunction "3_3") (pintype "bidirectional"))
      (node (ref "U6") (pin "P$6") (pinfunction "~{Y5}_P$6") (pintype "bidirectional"))
    )
    (net (code "21") (name "CTX7") (class "Default")
      (node (ref "CON25") (pin "3") (pinfunction "3_3") (pintype "bidirectional"))
      (node (ref "U6") (pin "P$7") (pinfunction "~{Y6}_P$7") (pintype "bidirectional"))
    )
    (net (code "22") (name "CTX8") (class "Default")
      (node (ref "CON26") (pin "3") (pinfunction "3_3") (pintype "bidirectional"))
      (node (ref "U6") (pin "P$8") (pinfunction "~{Y7}_P$8") (pintype "bidirectional"))
    )
    (net (code "23") (name "CTX9") (class "Default")
      (node (ref "CON27") (pin "3") (pinfunction "3_3") (pintype "bidirectional"))
      (node (ref "U6") (pin "P$9") (pinfunction "~{Y8}_P$9") (pintype "bidirectional"))
    )
    (net (code "24") (name "CTX10") (class "Default")
      (node (ref "CON28") (pin "3") (pinfunction "3_3") (pintype "bidirectional"))
      (node (ref "U6") (pin "P$10") (pinfunction "~{Y9}_P$10") (pintype "bidirectional"))
    )
    (net (code "25") (name "CTX11") (class "Default")
      (node (ref "CON3") (pin "3") (pinfunction "3_3") (pintype "bidirectional"))
      (node (ref "U6") (pin "P$11") (pinfunction "~{Y10}_P$11") (pintype "bidirectional"))
    )
    (net (code "26") (name "CTX12") (class "Default")
      (node (ref "CON4") (pin "3") (pinfunction "3_3") (pintype "bidirectional"))
      (node (ref "U6") (pin "P$13") (pinfunction "~{Y11}_P$13") (pintype "bidirectional"))
    )
    (net (code "27") (name "CTX13") (class "Default")
      (node (ref "CON5") (pin "3") (pinfunction "3_3") (pintype "bidirectional"))
      (node (ref "U6") (pin "P$14") (pinfunction "~{Y12}_P$14") (pintype "bidirectional"))
    )
    (net (code "28") (name "CTX14") (class "Default")
      (node (ref "CON6") (pin "3") (pinfunction "3_3") (pintype "bidirectional"))
      (node (ref "U6") (pin "P$15") (pinfunction "~{Y13}_P$15") (pintype "bidirectional"))
    )
    (net (code "29") (name "CTX15") (class "Default")
      (node (ref "CON7") (pin "3") (pinfunction "3_3") (pintype "bidirectional"))
      (node (ref "U6") (pin "P$16") (pinfunction "~{Y14}_P$16") (pintype "bidirectional"))
    )
    (net (code "30") (name "CTX16") (class "Default")
      (node (ref "CON8") (pin "3") (pinfunction "3_3") (pintype "bidirectional"))
      (node (ref "U6") (pin "P$17") (pinfunction "~{Y15}_P$17") (pintype "bidirectional"))
    )
    (net (code "31") (name "CURRENTSENSE") (class "Default")
      (node (ref "U2") (pin "7") (pinfunction "VIOUT_7") (pintype "bidirectional"))
    )
    (net (code "32") (name "DEBUG1") (class "Default")
      (node (ref "TST2") (pin "P$1") (pinfunction "P$1_P$1") (pintype "bidirectional"))
    )
    (net (code "33") (name "DEBUG2") (class "Default")
      (node (ref "TST1") (pin "P$1") (pinfunction "P$1_P$1") (pintype "bidirectional"))
    )
    (net (code "34") (name "GND") (class "Default")
      (node (ref "C1") (pin "2") (pinfunction "2_2") (pintype "passive"))
      (node (ref "C13") (pin "2") (pinfunction "2_2") (pintype "passive"))
      (node (ref "C14") (pin "2") (pinfunction "2_2") (pintype "passive"))
      (node (ref "C15") (pin "2") (pinfunction "2_2") (pintype "passive"))
      (node (ref "C16") (pin "2") (pinfunction "2_2") (pintype "passive"))
      (node (ref "C17") (pin "2") (pinfunction "2_2") (pintype "passive"))
      (node (ref "C18") (pin "2") (pinfunction "2_2") (pintype "passive"))
      (node (ref "C19") (pin "2") (pinfunction "2_2") (pintype "passive"))
      (node (ref "C20") (pin "2") (pinfunction "2_2") (pintype "passive"))
      (node (ref "C21") (pin "2") (pinfunction "2_2") (pintype "passive"))
      (node (ref "C22") (pin "2") (pinfunction "2_2") (pintype "passive"))
      (node (ref "C23") (pin "2") (pinfunction "2_2") (pintype "passive"))
      (node (ref "C24") (pin "2") (pinfunction "2_2") (pintype "passive"))
      (node (ref "C25") (pin "2") (pinfunction "2_2") (pintype "passive"))
      (node (ref "C4") (pin "2") (pinfunction "2_2") (pintype "passive"))
      (node (ref "C5") (pin "2") (pinfunction "2_2") (pintype "passive"))
      (node (ref "CON1") (pin "3") (pinfunction "GND_3") (pintype "bidirectional"))
      (node (ref "CON13") (pin "4") (pinfunction "4_4") (pintype "bidirectional"))
      (node (ref "CON14") (pin "3") (pinfunction "3_3") (pintype "bidirectional"))
      (node (ref "CON17") (pin "1") (pinfunction "1_1") (pintype "bidirectional"))
      (node (ref "CON19") (pin "1") (pinfunction "1_1") (pintype "bidirectional"))
      (node (ref "CON2") (pin "2") (pinfunction "2_2") (pintype "bidirectional"))
      (node (ref "CON20") (pin "1") (pinfunction "1_1") (pintype "bidirectional"))
      (node (ref "CON21") (pin "1") (pinfunction "1_1") (pintype "bidirectional"))
      (node (ref "CON22") (pin "1") (pinfunction "1_1") (pintype "bidirectional"))
      (node (ref "CON23") (pin "1") (pinfunction "1_1") (pintype "bidirectional"))
      (node (ref "CON24") (pin "1") (pinfunction "1_1") (pintype "bidirectional"))
      (node (ref "CON25") (pin "1") (pinfunction "1_1") (pintype "bidirectional"))
      (node (ref "CON26") (pin "1") (pinfunction "1_1") (pintype "bidirectional"))
      (node (ref "CON27") (pin "1") (pinfunction "1_1") (pintype "bidirectional"))
      (node (ref "CON28") (pin "1") (pinfunction "1_1") (pintype "bidirectional"))
      (node (ref "CON3") (pin "1") (pinfunction "1_1") (pintype "bidirectional"))
      (node (ref "CON4") (pin "1") (pinfunction "1_1") (pintype "bidirectional"))
      (node (ref "CON5") (pin "1") (pinfunction "1_1") (pintype "bidirectional"))
      (node (ref "CON6") (pin "1") (pinfunction "1_1") (pintype "bidirectional"))
      (node (ref "CON7") (pin "1") (pinfunction "1_1") (pintype "bidirectional"))
      (node (ref "CON8") (pin "1") (pinfunction "1_1") (pintype "bidirectional"))
      (node (ref "R15") (pin "1") (pinfunction "1_1") (pintype "passive"))
      (node (ref "R27") (pin "1") (pinfunction "1_1") (pintype "passive"))
      (node (ref "R36") (pin "2") (pinfunction "2_2") (pintype "passive"))
      (node (ref "R43") (pin "2") (pinfunction "2_2") (pintype "passive"))
      (node (ref "S1") (pin "1") (pinfunction "S_1") (pintype "passive"))
      (node (ref "S1") (pin "2") (pinfunction "S1_2") (pintype "passive"))
      (node (ref "T1") (pin "2") (pinfunction "S_2") (pintype "passive"))
      (node (ref "T4") (pin "2") (pinfunction "S_2") (pintype "passive"))
      (node (ref "T5") (pin "2") (pinfunction "S_2") (pintype "passive"))
      (node (ref "T6") (pin "2") (pinfunction "S_2") (pintype "passive"))
      (node (ref "T7") (pin "2") (pinfunction "S_2") (pintype "passive"))
      (node (ref "U2") (pin "5") (pinfunction "GND_5") (pintype "bidirectional"))
      (node (ref "U3") (pin "H3") (pinfunction "H-_H3") (pintype "bidirectional"))
      (node (ref "U3") (pin "V3") (pinfunction "V-_V3") (pintype "bidirectional"))
      (node (ref "U4") (pin "10") (pinfunction "GND_10") (pintype "bidirectional"))
      (node (ref "U5") (pin "P$22") (pinfunction "GND_P$22") (pintype "bidirectional"))
      (node (ref "U5") (pin "P$53") (pinfunction "GND_P$53") (pintype "bidirectional"))
      (node (ref "U5") (pin "P$63") (pinfunction "GND_P$63") (pintype "bidirectional"))
      (node (ref "U6") (pin "P$12") (pinfunction "GND_P$12") (pintype "bidirectional"))
      (node (ref "V1") (pin "2") (pinfunction "GND_2") (pintype "bidirectional"))
    )
    (net (code "35") (name "GREEN") (class "Default")
      (node (ref "CON16") (pin "2") (pinfunction "2_2") (pintype "bidirectional"))
      (node (ref "R22") (pin "1") (pinfunction "1_1") (pintype "passive"))
      (node (ref "T5") (pin "3") (pinfunction "D_3") (pintype "passive"))
    )
    (net (code "36") (name "HOLD") (class "Default")
      (node (ref "U4") (pin "1") (pinfunction "HOLD#/SIO3_1") (pintype "bidirectional"))
    )
    (net (code "37") (name "HORIZONTAL") (class "Default")
      (node (ref "U3") (pin "H2") (pinfunction "H_H2") (pintype "bidirectional"))
    )
    (net (code "38") (name "LED1") (class "Default")
      (node (ref "R26") (pin "1") (pinfunction "1_1") (pintype "passive"))
    )
    (net (code "39") (name "LED2") (class "Default")
      (node (ref "R29") (pin "1") (pinfunction "1_1") (pintype "passive"))
    )
    (net (code "40") (name "LED3") (class "Default")
      (node (ref "R30") (pin "1") (pinfunction "1_1") (pintype "passive"))
    )
    (net (code "41") (name "LED4") (class "Default")
      (node (ref "R34") (pin "2") (pinfunction "2_2") (pintype "passive"))
      (node (ref "U5") (pin "P$7") (pinfunction "PE5(OC3C/INT5)_P$7") (pintype "bidirectional"))
    )
    (net (code "42") (name "LED5") (class "Default")
      (node (ref "R35") (pin "2") (pinfunction "2_2") (pintype "passive"))
    )
    (net (code "43") (name "LED6") (class "Default")
      (node (ref "R32") (pin "2") (pinfunction "2_2") (pintype "passive"))
    )
    (net (code "44") (name "LED7") (class "Default")
      (node (ref "R33") (pin "2") (pinfunction "2_2") (pintype "passive"))
    )
    (net (code "45") (name "MISO") (class "Default")
      (node (ref "CON1") (pin "6") (pinfunction "MISO_6") (pintype "bidirectional"))
      (node (ref "U4") (pin "8") (pinfunction "SO/SIO1_8") (pintype "bidirectional"))
      (node (ref "U5") (pin "P$13") (pinfunction "PB3(MISO/PCINT3)_P$13") (pintype "bidirectional"))
    )
    (net (code "46") (name "MOSI") (class "Default")
      (node (ref "CON1") (pin "2") (pinfunction "MOSI_2") (pintype "bidirectional"))
      (node (ref "U4") (pin "15") (pinfunction "SI/SIO0_15") (pintype "bidirectional"))
      (node (ref "U5") (pin "P$12") (pinfunction "PB2(MOSI/PCINT2)_P$12") (pintype "bidirectional"))
    )
    (net (code "47") (name "Net-(B1--)") (class "Default")
      (node (ref "B1") (pin "2") (pinfunction "-_2") (pintype "bidirectional"))
      (node (ref "R8") (pin "1") (pinfunction "1_1") (pintype "passive"))
      (node (ref "T1") (pin "3") (pinfunction "D_3") (pintype "passive"))
    )
    (net (code "48") (name "Net-(CON3-Pad4)") (class "Default")
      (node (ref "CON3") (pin "4") (pinfunction "4_4") (pintype "bidirectional"))
      (node (ref "R37") (pin "2") (pinfunction "2_2") (pintype "passive"))
    )
    (net (code "49") (name "Net-(CON4-Pad4)") (class "Default")
      (node (ref "CON4") (pin "4") (pinfunction "4_4") (pintype "bidirectional"))
      (node (ref "R38") (pin "2") (pinfunction "2_2") (pintype "passive"))
    )
    (net (code "50") (name "Net-(CON5-Pad4)") (class "Default")
      (node (ref "CON5") (pin "4") (pinfunction "4_4") (pintype "bidirectional"))
      (node (ref "R39") (pin "2") (pinfunction "2_2") (pintype "passive"))
    )
    (net (code "51") (name "Net-(CON6-Pad4)") (class "Default")
      (node (ref "CON6") (pin "4") (pinfunction "4_4") (pintype "bidirectional"))
      (node (ref "R40") (pin "2") (pinfunction "2_2") (pintype "passive"))
    )
    (net (code "52") (name "Net-(CON7-Pad4)") (class "Default")
      (node (ref "CON7") (pin "4") (pinfunction "4_4") (pintype "bidirectional"))
      (node (ref "R41") (pin "2") (pinfunction "2_2") (pintype "passive"))
    )
    (net (code "53") (name "Net-(CON8-Pad4)") (class "Default")
      (node (ref "CON8") (pin "4") (pinfunction "4_4") (pintype "bidirectional"))
      (node (ref "R42") (pin "2") (pinfunction "2_2") (pintype "passive"))
    )
    (net (code "54") (name "Net-(CON15-Pad1)") (class "Default")
      (node (ref "CON15") (pin "1") (pinfunction "1_1") (pintype "bidirectional"))
      (node (ref "R16") (pin "1") (pinfunction "1_1") (pintype "passive"))
    )
    (net (code "55") (name "Net-(CON19-Pad4)") (class "Default")
      (node (ref "CON19") (pin "4") (pinfunction "4_4") (pintype "bidirectional"))
      (node (ref "R2") (pin "2") (pinfunction "2_2") (pintype "passive"))
    )
    (net (code "56") (name "Net-(CON20-Pad4)") (class "Default")
      (node (ref "CON20") (pin "4") (pinfunction "4_4") (pintype "bidirectional"))
      (node (ref "R3") (pin "2") (pinfunction "2_2") (pintype "passive"))
    )
    (net (code "57") (name "Net-(CON21-Pad4)") (class "Default")
      (node (ref "CON21") (pin "4") (pinfunction "4_4") (pintype "bidirectional"))
      (node (ref "R4") (pin "2") (pinfunction "2_2") (pintype "passive"))
    )
    (net (code "58") (name "Net-(CON22-Pad4)") (class "Default")
      (node (ref "CON22") (pin "4") (pinfunction "4_4") (pintype "bidirectional"))
      (node (ref "R5") (pin "2") (pinfunction "2_2") (pintype "passive"))
    )
    (net (code "59") (name "Net-(CON23-Pad4)") (class "Default")
      (node (ref "CON23") (pin "4") (pinfunction "4_4") (pintype "bidirectional"))
      (node (ref "R6") (pin "2") (pinfunction "2_2") (pintype "passive"))
    )
    (net (code "60") (name "Net-(CON24-Pad4)") (class "Default")
      (node (ref "CON24") (pin "4") (pinfunction "4_4") (pintype "bidirectional"))
      (node (ref "R9") (pin "2") (pinfunction "2_2") (pintype "passive"))
    )
    (net (code "61") (name "Net-(CON25-Pad4)") (class "Default")
      (node (ref "CON25") (pin "4") (pinfunction "4_4") (pintype "bidirectional"))
      (node (ref "R17") (pin "2") (pinfunction "2_2") (pintype "passive"))
    )
    (net (code "62") (name "Net-(CON26-Pad4)") (class "Default")
      (node (ref "CON26") (pin "4") (pinfunction "4_4") (pintype "bidirectional"))
      (node (ref "R18") (pin "2") (pinfunction "2_2") (pintype "passive"))
    )
    (net (code "63") (name "Net-(CON27-Pad4)") (class "Default")
      (node (ref "CON27") (pin "4") (pinfunction "4_4") (pintype "bidirectional"))
      (node (ref "R19") (pin "2") (pinfunction "2_2") (pintype "passive"))
    )
    (net (code "64") (name "Net-(CON28-Pad4)") (class "Default")
      (node (ref "CON28") (pin "4") (pinfunction "4_4") (pintype "bidirectional"))
      (node (ref "R20") (pin "2") (pinfunction "2_2") (pintype "passive"))
    )
    (net (code "65") (name "Net-(LED1-BLUECATHODE)") (class "Default")
      (node (ref "LED1") (pin "3") (pinfunction "BLUECATHODE_3") (pintype "passive"))
      (node (ref "R21") (pin "2") (pinfunction "2_2") (pintype "passive"))
    )
    (net (code "66") (name "Net-(LED1-GREENCATHODE)") (class "Default")
      (node (ref "LED1") (pin "4") (pinfunction "GREENCATHODE_4") (pintype "passive"))
      (node (ref "R22") (pin "2") (pinfunction "2_2") (pintype "passive"))
    )
    (net (code "67") (name "Net-(LED1-REDCATHODE)") (class "Default")
      (node (ref "LED1") (pin "1") (pinfunction "REDCATHODE_1") (pintype "passive"))
      (node (ref "R1") (pin "2") (pinfunction "2_2") (pintype "passive"))
    )
    (net (code "68") (name "Net-(LED2-A)") (class "Default")
      (node (ref "C12") (pin "1") (pinfunction "1_1") (pintype "passive"))
      (node (ref "C2") (pin "1") (pinfunction "1_1") (pintype "passive"))
      (node (ref "C6") (pin "1") (pinfunction "1_1") (pintype "passive"))
      (node (ref "C7") (pin "1") (pinfunction "1_1") (pintype "passive"))
      (node (ref "C8") (pin "1") (pinfunction "1_1") (pintype "passive"))
      (node (ref "C9") (pin "1") (pinfunction "1_1") (pintype "passive"))
      (node (ref "CON15") (pin "2") (pinfunction "2_2") (pintype "bidirectional"))
      (node (ref "LED2") (pin "1") (pinfunction "A_1") (pintype "passive"))
      (node (ref "LED3") (pin "1") (pinfunction "A_1") (pintype "passive"))
      (node (ref "LED4") (pin "1") (pinfunction "A_1") (pintype "passive"))
      (node (ref "LED5") (pin "1") (pinfunction "A_1") (pintype "passive"))
      (node (ref "LED6") (pin "1") (pinfunction "A_1") (pintype "passive"))
      (node (ref "LED7") (pin "1") (pinfunction "A_1") (pintype "passive"))
    )
    (net (code "69") (name "Net-(LED2-C)") (class "Default")
      (node (ref "LED2") (pin "2") (pinfunction "C_2") (pintype "passive"))
      (node (ref "R10") (pin "2") (pinfunction "2_2") (pintype "passive"))
    )
    (net (code "70") (name "Net-(LED3-C)") (class "Default")
      (node (ref "LED3") (pin "2") (pinfunction "C_2") (pintype "passive"))
      (node (ref "R11") (pin "2") (pinfunction "2_2") (pintype "passive"))
    )
    (net (code "71") (name "Net-(LED4-C)") (class "Default")
      (node (ref "LED4") (pin "2") (pinfunction "C_2") (pintype "passive"))
      (node (ref "R12") (pin "2") (pinfunction "2_2") (pintype "passive"))
    )
    (net (code "72") (name "Net-(LED5-C)") (class "Default")
      (node (ref "LED5") (pin "2") (pinfunction "C_2") (pintype "passive"))
      (node (ref "R13") (pin "2") (pinfunction "2_2") (pintype "passive"))
    )
    (net (code "73") (name "Net-(LED6-C)") (class "Default")
      (node (ref "LED6") (pin "2") (pinfunction "C_2") (pintype "passive"))
      (node (ref "R14") (pin "2") (pinfunction "2_2") (pintype "passive"))
    )
    (net (code "74") (name "Net-(LED7-C)") (class "Default")
      (node (ref "LED7") (pin "2") (pinfunction "C_2") (pintype "passive"))
      (node (ref "R25") (pin "2") (pinfunction "2_2") (pintype "passive"))
    )
    (net (code "75") (name "Net-(LED8-C)") (class "Default")
      (node (ref "LED8") (pin "1") (pinfunction "C_1") (pintype "passive"))
      (node (ref "R32") (pin "1") (pinfunction "1_1") (pintype "passive"))
    )
    (net (code "76") (name "Net-(LED9-C)") (class "Default")
      (node (ref "LED9") (pin "1") (pinfunction "C_1") (pintype "passive"))
      (node (ref "R33") (pin "1") (pinfunction "1_1") (pintype "passive"))
    )
    (net (code "77") (name "Net-(LED10-A)") (class "Default")
      (node (ref "LED10") (pin "2") (pinfunction "A_2") (pintype "passive"))
      (node (ref "T3") (pin "5") (pinfunction "D_5") (pintype "passive"))
      (node (ref "T3") (pin "6") (pinfunction "D_6") (pintype "passive"))
      (node (ref "T3") (pin "7") (pinfunction "D_7") (pintype "passive"))
      (node (ref "T3") (pin "8") (pinfunction "D_8") (pintype "passive"))
      (node (ref "U2") (pin "1") (pinfunction "IP+_1") (pintype "bidirectional"))
      (node (ref "U2") (pin "2") (pinfunction "IP+_2") (pintype "bidirectional"))
    )
    (net (code "78") (name "Net-(LED10-C)") (class "Default")
      (node (ref "LED10") (pin "1") (pinfunction "C_1") (pintype "passive"))
      (node (ref "R27") (pin "2") (pinfunction "2_2") (pintype "passive"))
    )
    (net (code "79") (name "Net-(LED11-C)") (class "Default")
      (node (ref "LED11") (pin "1") (pinfunction "C_1") (pintype "passive"))
      (node (ref "R34") (pin "1") (pinfunction "1_1") (pintype "passive"))
    )
    (net (code "80") (name "Net-(LED12-C)") (class "Default")
      (node (ref "LED12") (pin "1") (pinfunction "C_1") (pintype "passive"))
      (node (ref "R35") (pin "1") (pinfunction "1_1") (pintype "passive"))
    )
    (net (code "81") (name "Net-(LED13-C)") (class "Default")
      (node (ref "LED13") (pin "1") (pinfunction "C_1") (pintype "passive"))
      (node (ref "R36") (pin "1") (pinfunction "1_1") (pintype "passive"))
    )
    (net (code "82") (name "Net-(T1-G)") (class "Default")
      (node (ref "R28") (pin "2") (pinfunction "2_2") (pintype "passive"))
      (node (ref "T1") (pin "1") (pinfunction "G_1") (pintype "passive"))
    )
    (net (code "83") (name "Net-(T2-D)") (class "Default")
      (node (ref "R10") (pin "1") (pinfunction "1_1") (pintype "passive"))
      (node (ref "R11") (pin "1") (pinfunction "1_1") (pintype "passive"))
      (node (ref "R12") (pin "1") (pinfunction "1_1") (pintype "passive"))
      (node (ref "R13") (pin "1") (pinfunction "1_1") (pintype "passive"))
      (node (ref "R14") (pin "1") (pinfunction "1_1") (pintype "passive"))
      (node (ref "R25") (pin "1") (pinfunction "1_1") (pintype "passive"))
      (node (ref "T2") (pin "3") (pinfunction "D_3") (pintype "passive"))
    )
    (net (code "84") (name "Net-(T2-G)") (class "Default")
      (node (ref "R16") (pin "2") (pinfunction "2_2") (pintype "passive"))
      (node (ref "T2") (pin "1") (pinfunction "G_1") (pintype "passive"))
    )
    (net (code "85") (name "Net-(T2-S)") (class "Default")
      (node (ref "C12") (pin "2") (pinfunction "2_2") (pintype "passive"))
      (node (ref "C2") (pin "2") (pinfunction "2_2") (pintype "passive"))
      (node (ref "C6") (pin "2") (pinfunction "2_2") (pintype "passive"))
      (node (ref "C7") (pin "2") (pinfunction "2_2") (pintype "passive"))
      (node (ref "C8") (pin "2") (pinfunction "2_2") (pintype "passive"))
      (node (ref "C9") (pin "2") (pinfunction "2_2") (pintype "passive"))
      (node (ref "CON15") (pin "3") (pinfunction "3_3") (pintype "bidirectional"))
      (node (ref "T2") (pin "2") (pinfunction "S_2") (pintype "passive"))
    )
    (net (code "86") (name "Net-(T3-G)") (class "Default")
      (node (ref "R24") (pin "1") (pinfunction "1_1") (pintype "passive"))
      (node (ref "T3") (pin "4") (pinfunction "G_4") (pintype "passive"))
      (node (ref "T7") (pin "3") (pinfunction "D_3") (pintype "passive"))
    )
    (net (code "87") (name "Net-(T4-G)") (class "Default")
      (node (ref "R26") (pin "2") (pinfunction "2_2") (pintype "passive"))
      (node (ref "T4") (pin "1") (pinfunction "G_1") (pintype "passive"))
    )
    (net (code "88") (name "Net-(T5-G)") (class "Default")
      (node (ref "R29") (pin "2") (pinfunction "2_2") (pintype "passive"))
      (node (ref "T5") (pin "1") (pinfunction "G_1") (pintype "passive"))
    )
    (net (code "89") (name "Net-(T6-G)") (class "Default")
      (node (ref "R30") (pin "2") (pinfunction "2_2") (pintype "passive"))
      (node (ref "T6") (pin "1") (pinfunction "G_1") (pintype "passive"))
    )
    (net (code "90") (name "Net-(T7-G)") (class "Default")
      (node (ref "R31") (pin "1") (pinfunction "1_1") (pintype "passive"))
      (node (ref "T7") (pin "1") (pinfunction "G_1") (pintype "passive"))
    )
    (net (code "91") (name "Net-(U$3-A)") (class "Default")
      (node (ref "U$3") (pin "1") (pinfunction "A_1") (pintype "passive"))
      (node (ref "U$4") (pin "1") (pinfunction "A_1") (pintype "passive"))
      (node (ref "U2") (pin "3") (pinfunction "IP-_3") (pintype "bidirectional"))
      (node (ref "U2") (pin "4") (pinfunction "IP-_4") (pintype "bidirectional"))
    )
    (net (code "92") (name "Net-(U5-PD0(SCL{slash}INT0))") (class "Default")
      (node (ref "CON13") (pin "2") (pinfunction "2_2") (pintype "bidirectional"))
      (node (ref "U5") (pin "P$25") (pinfunction "PD0(SCL/INT0)_P$25") (pintype "bidirectional"))
    )
    (net (code "93") (name "Net-(U5-PD1(SDA{slash}INT1))") (class "Default")
      (node (ref "CON13") (pin "3") (pinfunction "3_3") (pintype "bidirectional"))
      (node (ref "U5") (pin "P$26") (pinfunction "PD1(SDA/INT1)_P$26") (pintype "bidirectional"))
    )
    (net (code "94") (name "Net-(U5-PD2(RXD1{slash}INT2))") (class "Default")
      (node (ref "CON17") (pin "2") (pinfunction "2_2") (pintype "bidirectional"))
      (node (ref "U5") (pin "P$27") (pinfunction "PD2(RXD1/INT2)_P$27") (pintype "bidirectional"))
    )
    (net (code "95") (name "Net-(U5-PD3(TXD1{slash}INT3))") (class "Default")
      (node (ref "CON17") (pin "3") (pinfunction "3_3") (pintype "bidirectional"))
      (node (ref "U5") (pin "P$28") (pinfunction "PD3(TXD1/INT3)_P$28") (pintype "bidirectional"))
    )
    (net (code "96") (name "Net-(U5-XTAL1)") (class "Default")
      (node (ref "C23") (pin "1") (pinfunction "1_1") (pintype "passive"))
      (node (ref "U5") (pin "P$24") (pinfunction "XTAL1_P$24") (pintype "bidirectional"))
      (node (ref "XTAL2") (pin "1") (pinfunction "1_1") (pintype "passive"))
    )
    (net (code "97") (name "Net-(U5-XTAL2)") (class "Default")
      (node (ref "C22") (pin "1") (pinfunction "1_1") (pintype "passive"))
      (node (ref "U5") (pin "P$23") (pinfunction "XTAL2_P$23") (pintype "bidirectional"))
      (node (ref "XTAL2") (pin "2") (pinfunction "2_2") (pintype "passive"))
    )
    (net (code "98") (name "Net-(U6-~{E2})") (class "Default")
      (node (ref "R43") (pin "1") (pinfunction "1_1") (pintype "passive"))
      (node (ref "U6") (pin "P$19") (pinfunction "~{E2}_P$19") (pintype "bidirectional"))
    )
    (net (code "99") (name "RED") (class "Default")
      (node (ref "CON16") (pin "3") (pinfunction "3_3") (pintype "bidirectional"))
      (node (ref "R1") (pin "1") (pinfunction "1_1") (pintype "passive"))
      (node (ref "T6") (pin "3") (pinfunction "D_3") (pintype "passive"))
    )
    (net (code "100") (name "RESET") (class "Default")
      (node (ref "C14") (pin "1") (pinfunction "1_1") (pintype "passive"))
      (node (ref "CON1") (pin "4") (pinfunction "~{RESET}_4") (pintype "bidirectional"))
      (node (ref "R7") (pin "2") (pinfunction "2_2") (pintype "passive"))
      (node (ref "S1") (pin "3") (pinfunction "P_3") (pintype "passive"))
      (node (ref "S1") (pin "4") (pinfunction "P1_4") (pintype "passive"))
      (node (ref "U5") (pin "P$20") (pinfunction "~{RESET}_P$20") (pintype "bidirectional"))
    )
    (net (code "101") (name "SCK") (class "Default")
      (node (ref "CON1") (pin "5") (pinfunction "SCK_5") (pintype "bidirectional"))
      (node (ref "U4") (pin "16") (pinfunction "SCLK_16") (pintype "bidirectional"))
      (node (ref "U5") (pin "P$11") (pinfunction "PB1(SCK/PCINT1)_P$11") (pintype "bidirectional"))
    )
    (net (code "102") (name "TRANSMITLEDS") (class "Default")
      (node (ref "CON14") (pin "1") (pinfunction "1_1") (pintype "bidirectional"))
    )
    (net (code "103") (name "VERTICAL") (class "Default")
      (node (ref "U3") (pin "V2") (pinfunction "V_V2") (pintype "bidirectional"))
    )
    (net (code "104") (name "WP") (class "Default")
      (node (ref "U4") (pin "9") (pinfunction "WP#/SIO2_9") (pintype "bidirectional"))
    )
    (net (code "105") (name "unconnected-(U2-~{FAULT}-Pad6)") (class "Default")
      (node (ref "U2") (pin "6") (pinfunction "~{FAULT}_6") (pintype "bidirectional"))
    )
    (net (code "106") (name "unconnected-(U5-PA0(AD0)-PadP$51)") (class "Default")
      (node (ref "U5") (pin "P$51") (pinfunction "PA0(AD0)_P$51") (pintype "bidirectional"))
    )
    (net (code "107") (name "unconnected-(U5-PA1(AD1)-PadP$50)") (class "Default")
      (node (ref "U5") (pin "P$50") (pinfunction "PA1(AD1)_P$50") (pintype "bidirectional"))
    )
    (net (code "108") (name "unconnected-(U5-PA2(AD2)-PadP$49)") (class "Default")
      (node (ref "U5") (pin "P$49") (pinfunction "PA2(AD2)_P$49") (pintype "bidirectional"))
    )
    (net (code "109") (name "unconnected-(U5-PA3(AD3)-PadP$48)") (class "Default")
      (node (ref "U5") (pin "P$48") (pinfunction "PA3(AD3)_P$48") (pintype "bidirectional"))
    )
    (net (code "110") (name "unconnected-(U5-PA4(AD4)-PadP$47)") (class "Default")
      (node (ref "U5") (pin "P$47") (pinfunction "PA4(AD4)_P$47") (pintype "bidirectional"))
    )
    (net (code "111") (name "unconnected-(U5-PA5(AD5)-PadP$46)") (class "Default")
      (node (ref "U5") (pin "P$46") (pinfunction "PA5(AD5)_P$46") (pintype "bidirectional"))
    )
    (net (code "112") (name "unconnected-(U5-PA6(AD6)-PadP$45)") (class "Default")
      (node (ref "U5") (pin "P$45") (pinfunction "PA6(AD6)_P$45") (pintype "bidirectional"))
    )
    (net (code "113") (name "unconnected-(U5-PA7(AD7)-PadP$44)") (class "Default")
      (node (ref "U5") (pin "P$44") (pinfunction "PA7(AD7)_P$44") (pintype "bidirectional"))
    )
    (net (code "114") (name "unconnected-(U5-PB0(~{SS}{slash}PCINT0)-PadP$10)") (class "Default")
      (node (ref "U5") (pin "P$10") (pinfunction "PB0(~{SS}/PCINT0)_P$10") (pintype "bidirectional"))
    )
    (net (code "115") (name "unconnected-(U5-PB4(OC2A{slash}PCINT4)-PadP$14)") (class "Default")
      (node (ref "U5") (pin "P$14") (pinfunction "PB4(OC2A/PCINT4)_P$14") (pintype "bidirectional"))
    )
    (net (code "116") (name "unconnected-(U5-PB5(OC1A{slash}PCINT5)-PadP$15)") (class "Default")
      (node (ref "U5") (pin "P$15") (pinfunction "PB5(OC1A/PCINT5)_P$15") (pintype "bidirectional"))
    )
    (net (code "117") (name "unconnected-(U5-PB6(OC1B{slash}PCINT6)-PadP$16)") (class "Default")
      (node (ref "U5") (pin "P$16") (pinfunction "PB6(OC1B/PCINT6)_P$16") (pintype "bidirectional"))
    )
    (net (code "118") (name "unconnected-(U5-PB7(OC0A{slash}OC1C{slash}PCINT7)-PadP$17)") (class "Default")
      (node (ref "U5") (pin "P$17") (pinfunction "PB7(OC0A/OC1C/PCINT7)_P$17") (pintype "bidirectional"))
    )
    (net (code "119") (name "unconnected-(U5-PC0(A8)-PadP$35)") (class "Default")
      (node (ref "U5") (pin "P$35") (pinfunction "PC0(A8)_P$35") (pintype "bidirectional"))
    )
    (net (code "120") (name "unconnected-(U5-PC1(A9)-PadP$36)") (class "Default")
      (node (ref "U5") (pin "P$36") (pinfunction "PC1(A9)_P$36") (pintype "bidirectional"))
    )
    (net (code "121") (name "unconnected-(U5-PC2(A10)-PadP$37)") (class "Default")
      (node (ref "U5") (pin "P$37") (pinfunction "PC2(A10)_P$37") (pintype "bidirectional"))
    )
    (net (code "122") (name "unconnected-(U5-PC3(A11)-PadP$38)") (class "Default")
      (node (ref "U5") (pin "P$38") (pinfunction "PC3(A11)_P$38") (pintype "bidirectional"))
    )
    (net (code "123") (name "unconnected-(U5-PC4(A12)-PadP$39)") (class "Default")
      (node (ref "U5") (pin "P$39") (pinfunction "PC4(A12)_P$39") (pintype "bidirectional"))
    )
    (net (code "124") (name "unconnected-(U5-PC5(A13)-PadP$40)") (class "Default")
      (node (ref "U5") (pin "P$40") (pinfunction "PC5(A13)_P$40") (pintype "bidirectional"))
    )
    (net (code "125") (name "unconnected-(U5-PC6(A14)-PadP$41)") (class "Default")
      (node (ref "U5") (pin "P$41") (pinfunction "PC6(A14)_P$41") (pintype "bidirectional"))
    )
    (net (code "126") (name "unconnected-(U5-PC7(A15)-PadP$42)") (class "Default")
      (node (ref "U5") (pin "P$42") (pinfunction "PC7(A15)_P$42") (pintype "bidirectional"))
    )
    (net (code "127") (name "unconnected-(U5-PD4(ICP1)-PadP$29)") (class "Default")
      (node (ref "U5") (pin "P$29") (pinfunction "PD4(ICP1)_P$29") (pintype "bidirectional"))
    )
    (net (code "128") (name "unconnected-(U5-PD5(XCK1)-PadP$30)") (class "Default")
      (node (ref "U5") (pin "P$30") (pinfunction "PD5(XCK1)_P$30") (pintype "bidirectional"))
    )
    (net (code "129") (name "unconnected-(U5-PD6(T1)-PadP$31)") (class "Default")
      (node (ref "U5") (pin "P$31") (pinfunction "PD6(T1)_P$31") (pintype "bidirectional"))
    )
    (net (code "130") (name "unconnected-(U5-PD7(T0)-PadP$32)") (class "Default")
      (node (ref "U5") (pin "P$32") (pinfunction "PD7(T0)_P$32") (pintype "bidirectional"))
    )
    (net (code "131") (name "unconnected-(U5-PE2(XCK0{slash}AIN0)-PadP$4)") (class "Default")
      (node (ref "U5") (pin "P$4") (pinfunction "PE2(XCK0/AIN0)_P$4") (pintype "bidirectional"))
    )
    (net (code "132") (name "unconnected-(U5-PE3(OC3A{slash}AIN1)-PadP$5)") (class "Default")
      (node (ref "U5") (pin "P$5") (pinfunction "PE3(OC3A/AIN1)_P$5") (pintype "bidirectional"))
    )
    (net (code "133") (name "unconnected-(U5-PE4(OC3B{slash}INT4)-PadP$6)") (class "Default")
      (node (ref "U5") (pin "P$6") (pinfunction "PE4(OC3B/INT4)_P$6") (pintype "bidirectional"))
    )
    (net (code "134") (name "unconnected-(U5-PE6(T3{slash}INT6)-PadP$8)") (class "Default")
      (node (ref "U5") (pin "P$8") (pinfunction "PE6(T3/INT6)_P$8") (pintype "bidirectional"))
    )
    (net (code "135") (name "unconnected-(U5-PE7(ICP3{slash}CLKO{slash}INT7)-PadP$9)") (class "Default")
      (node (ref "U5") (pin "P$9") (pinfunction "PE7(ICP3/CLKO/INT7)_P$9") (pintype "bidirectional"))
    )
    (net (code "136") (name "unconnected-(U5-PF0(ADC0)-PadP$61)") (class "Default")
      (node (ref "U5") (pin "P$61") (pinfunction "PF0(ADC0)_P$61") (pintype "bidirectional"))
    )
    (net (code "137") (name "unconnected-(U5-PF1(ADC1)-PadP$60)") (class "Default")
      (node (ref "U5") (pin "P$60") (pinfunction "PF1(ADC1)_P$60") (pintype "bidirectional"))
    )
    (net (code "138") (name "unconnected-(U5-PF2(ADC2)-PadP$59)") (class "Default")
      (node (ref "U5") (pin "P$59") (pinfunction "PF2(ADC2)_P$59") (pintype "bidirectional"))
    )
    (net (code "139") (name "unconnected-(U5-PF3(ADC3)-PadP$58)") (class "Default")
      (node (ref "U5") (pin "P$58") (pinfunction "PF3(ADC3)_P$58") (pintype "bidirectional"))
    )
    (net (code "140") (name "unconnected-(U5-PF4(ADC4{slash}TCK)-PadP$57)") (class "Default")
      (node (ref "U5") (pin "P$57") (pinfunction "PF4(ADC4/TCK)_P$57") (pintype "bidirectional"))
    )
    (net (code "141") (name "unconnected-(U5-PF5(ADC5{slash}TMS)-PadP$56)") (class "Default")
      (node (ref "U5") (pin "P$56") (pinfunction "PF5(ADC5/TMS)_P$56") (pintype "bidirectional"))
    )
    (net (code "142") (name "unconnected-(U5-PF6(ADC6{slash}TDO)-PadP$55)") (class "Default")
      (node (ref "U5") (pin "P$55") (pinfunction "PF6(ADC6/TDO)_P$55") (pintype "bidirectional"))
    )
    (net (code "143") (name "unconnected-(U5-PF7(ADC7{slash}TDI)-PadP$54)") (class "Default")
      (node (ref "U5") (pin "P$54") (pinfunction "PF7(ADC7/TDI)_P$54") (pintype "bidirectional"))
    )
    (net (code "144") (name "unconnected-(U5-PG0(~{WR})-PadP$33)") (class "Default")
      (node (ref "U5") (pin "P$33") (pinfunction "PG0(~{WR})_P$33") (pintype "bidirectional"))
    )
    (net (code "145") (name "unconnected-(U5-PG1(~{RD})-PadP$34)") (class "Default")
      (node (ref "U5") (pin "P$34") (pinfunction "PG1(~{RD})_P$34") (pintype "bidirectional"))
    )
    (net (code "146") (name "unconnected-(U5-PG2(ALE)-PadP$43)") (class "Default")
      (node (ref "U5") (pin "P$43") (pinfunction "PG2(ALE)_P$43") (pintype "bidirectional"))
    )
    (net (code "147") (name "unconnected-(U5-PG3(TOSC2)-PadP$18)") (class "Default")
      (node (ref "U5") (pin "P$18") (pinfunction "PG3(TOSC2)_P$18") (pintype "bidirectional"))
    )
    (net (code "148") (name "unconnected-(U5-PG4(TOSC1)-PadP$19)") (class "Default")
      (node (ref "U5") (pin "P$19") (pinfunction "PG4(TOSC1)_P$19") (pintype "bidirectional"))
    )
  )
)
